# AIL_TSAL_Schem.net
KiCad netlist of a schematic drawn in Altium Designer
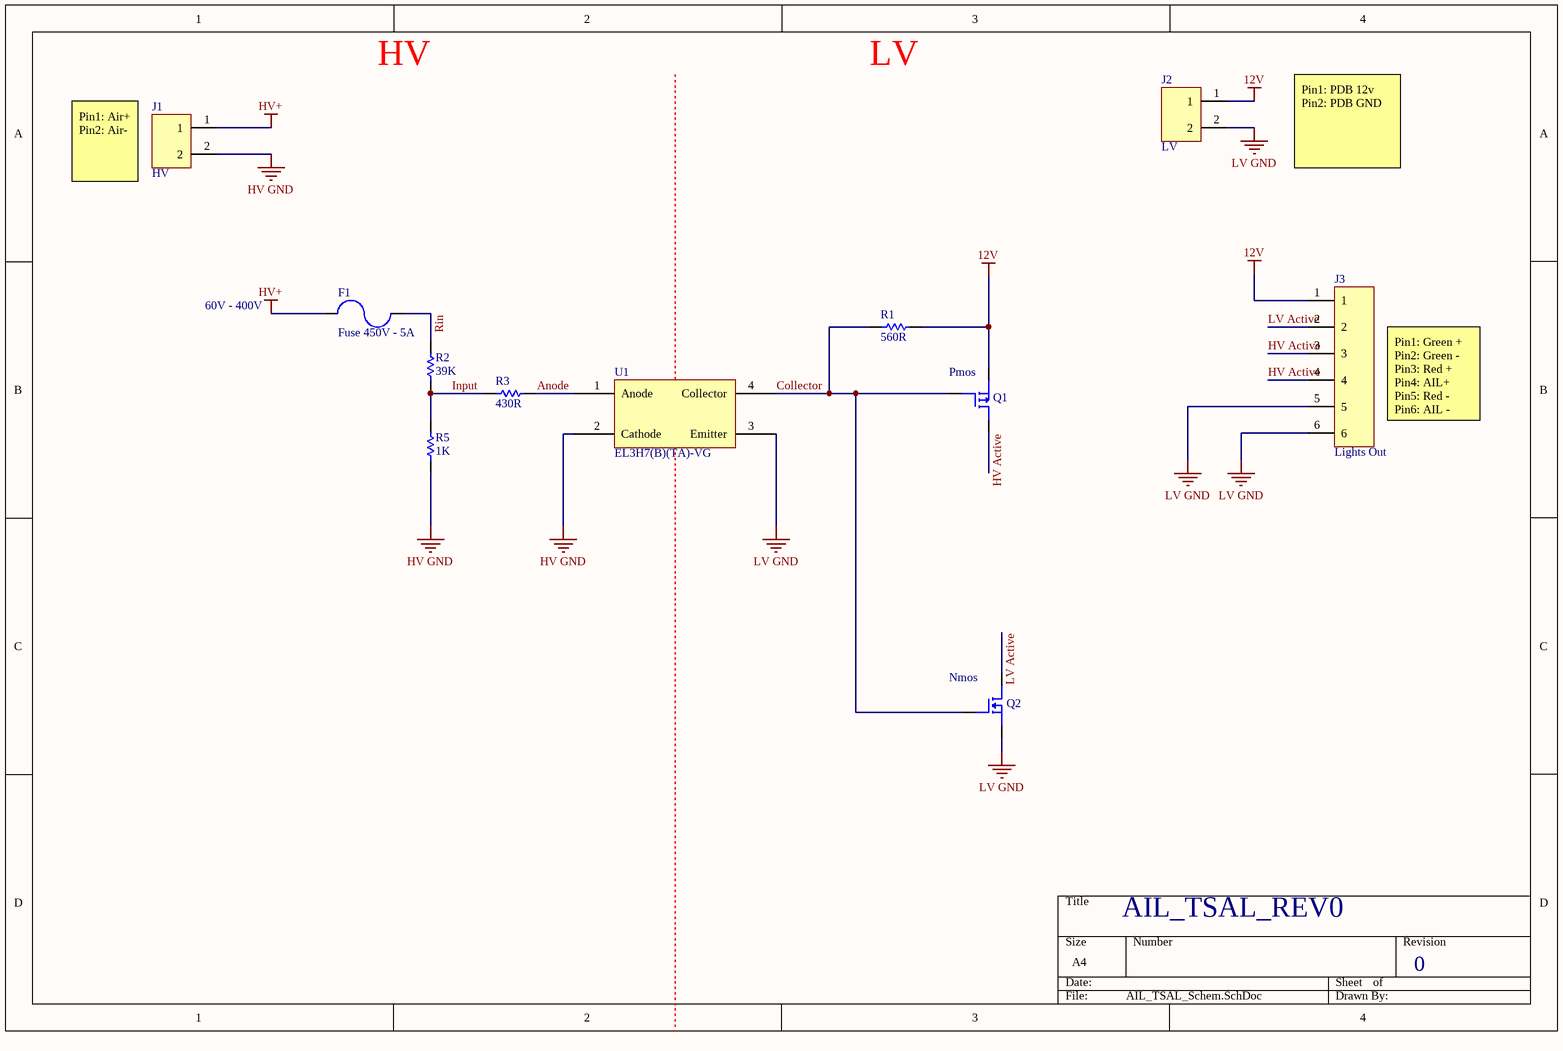
[diagram p0: AIL_TSAL_Schem.SchDoc]

(export (version "E")
  (design (tool "Eeschema 10.0.6"))
  (components
    (comp (ref "F1")
      (value "Fuse 450V - 5A")
      (footprint "Fuse-11.2x5.05")
      (description "FUSE 500VDC 350VAC SMT 5A")
      (libsource (lib "Misc") (part "Fuse 450V - 5A"))
    )
    (comp (ref "J1")
      (value "HV")
      (footprint "2PIN")
      (description "CONN HEADER R/A 2POS 2.54MM")
      (fields (field (name "MANUFACTURER") "Molex") (field (name "MANUFACTURER PART NUMBER") "0705530106"))
      (libsource (lib "Connectors") (part "2PIN"))
    )
    (comp (ref "J2")
      (value "LV")
      (footprint "2PIN")
      (description "CONN HEADER R/A 2POS 2.54MM")
      (fields (field (name "MANUFACTURER") "Molex") (field (name "MANUFACTURER PART NUMBER") "0705530106"))
      (libsource (lib "Connectors") (part "2PIN"))
    )
    (comp (ref "J3")
      (value "Lights Out")
      (footprint "6PIN")
      (description "CONN HEADER R/A 6POS 2.54MM")
      (fields (field (name "MANUFACTURER") "Molex") (field (name "MANUFACTURER PART NUMBER") "70553-0040"))
      (libsource (lib "Connectors") (part "6PIN"))
    )
    (comp (ref "Q1")
      (value "NTD2955T4GOSCT-ND")
      (footprint "DPAK-TO252")
      (description "MOSFET P-CH 60V 12A DPAK")
      (fields
        (field (name "MANUFACTURER") "ON Semiconductor")
        (field (name "MANUFACTURER PART NUMBER") "NTD2955T4G")
      )
      (libsource (lib "Transistors") (part "P-FET-60V-12A"))
    )
    (comp (ref "Q2")
      (value "IPD50N06S4L12ATMA2CT-ND")
      (footprint "DPAK-TO252")
      (description "MOSFET N-CH 60V 50A TO252-3")
      (fields
        (field (name "MANUFACTURER") "Infineon")
        (field (name "MANUFACTURER PART NUMBER") "IPD50N06S4L12ATMA2")
      )
      (libsource (lib "Transistors") (part "N-FET-60V-50A"))
    )
    (comp (ref "R1")
      (value "560R")
      (footprint "RES-0603")
      (description "RES 560 OHM 1% 1/10W 0603")
      (libsource (lib "Resistors") (part "0603 - 560R"))
    )
    (comp (ref "R2")
      (value "39K")
      (footprint "RES-0603")
      (description "RES SMD 39K OHM 1% 1/10W")
      (fields
        (field (name "MANUFACTURER") "TE Connectivity")
        (field (name "MANUFACTURER PART NUMBER") "CRGCQ0603F39K")
      )
      (libsource (lib "Resistors") (part "0603-39KR"))
    )
    (comp (ref "R3")
      (value "430R")
      (footprint "RES-0603")
      (description "RES 430 OHM 1% 1/10W 0603")
      (libsource (lib "Resistors") (part "0603 - 430R"))
    )
    (comp (ref "R5")
      (value "1K")
      (footprint "RES-0603")
      (description "RES SMD 1K OHM 1% 1/10W 0603")
      (fields
        (field (name "MANUFACTURER") "Vishay Dale")
        (field (name "MANUFACTURER PART NUMBER") "CRCW06031K00FKEA")
      )
      (libsource (lib "Resistors") (part "0603-1KR"))
    )
    (comp (ref "U1")
      (value "EL3H7(B)(TA)-VG")
      (footprint "SOIC127P700X200-4N")
      (description "OPTOISOLATOR 3.75KV TRANS 4-SSOP")
      (fields (field (name "MANUFACTURER") "Everlight"))
      (libsource (lib "Schlib1_TSAL") (part "EL3H7(B)(TA)-VG"))
    )
  )
  (nets
    (net (code "1") (name "/Anode") (class "Default")
      (node (ref "R3") (pin "2") (pinfunction "2_2") (pintype "passive"))
      (node (ref "U1") (pin "1") (pinfunction "Anode_1") (pintype "passive"))
    )
    (net (code "2") (name "/Collector") (class "Default")
      (node (ref "Q1") (pin "1") (pinfunction "1_1") (pintype "passive"))
      (node (ref "Q2") (pin "1") (pinfunction "1_1") (pintype "passive"))
      (node (ref "R1") (pin "1") (pinfunction "1_1") (pintype "passive"))
      (node (ref "U1") (pin "4") (pinfunction "Collector_4") (pintype "passive"))
    )
    (net (code "3") (name "/HV Active") (class "Default")
      (node (ref "J3") (pin "3") (pinfunction "3_3") (pintype "passive"))
      (node (ref "J3") (pin "4") (pinfunction "4_4") (pintype "passive"))
      (node (ref "Q1") (pin "2") (pinfunction "2_2") (pintype "passive"))
    )
    (net (code "4") (name "/Input") (class "Default")
      (node (ref "R2") (pin "1") (pinfunction "1_1") (pintype "passive"))
      (node (ref "R3") (pin "1") (pinfunction "1_1") (pintype "passive"))
      (node (ref "R5") (pin "2") (pinfunction "2_2") (pintype "passive"))
    )
    (net (code "5") (name "/LV Active") (class "Default")
      (node (ref "J3") (pin "2") (pinfunction "2_2") (pintype "passive"))
      (node (ref "Q2") (pin "2") (pinfunction "2_2") (pintype "passive"))
    )
    (net (code "6") (name "/Rin") (class "Default")
      (node (ref "F1") (pin "2") (pinfunction "2_2") (pintype "passive"))
      (node (ref "R2") (pin "2") (pinfunction "2_2") (pintype "passive"))
    )
    (net (code "7") (name "12V") (class "Default")
      (node (ref "J2") (pin "1") (pinfunction "1_1") (pintype "passive"))
      (node (ref "J3") (pin "1") (pinfunction "1_1") (pintype "passive"))
      (node (ref "Q1") (pin "3") (pinfunction "3_3") (pintype "passive"))
      (node (ref "R1") (pin "2") (pinfunction "2_2") (pintype "passive"))
    )
    (net (code "8") (name "HV GND") (class "Default")
      (node (ref "J1") (pin "2") (pinfunction "2_2") (pintype "passive"))
      (node (ref "R5") (pin "1") (pinfunction "1_1") (pintype "passive"))
      (node (ref "U1") (pin "2") (pinfunction "Cathode_2") (pintype "passive"))
    )
    (net (code "9") (name "HV+") (class "Default")
      (node (ref "F1") (pin "1") (pinfunction "1_1") (pintype "passive"))
      (node (ref "J1") (pin "1") (pinfunction "1_1") (pintype "passive"))
    )
    (net (code "10") (name "LV GND") (class "Default")
      (node (ref "J2") (pin "2") (pinfunction "2_2") (pintype "passive"))
      (node (ref "J3") (pin "5") (pinfunction "5_5") (pintype "passive"))
      (node (ref "J3") (pin "6") (pinfunction "6_6") (pintype "passive"))
      (node (ref "Q2") (pin "3") (pinfunction "3_3") (pintype "passive"))
      (node (ref "U1") (pin "3") (pinfunction "Emitter_3") (pintype "passive"))
    )
  )
)
